# uController.net
KiCad netlist of a schematic drawn in Altium Designer
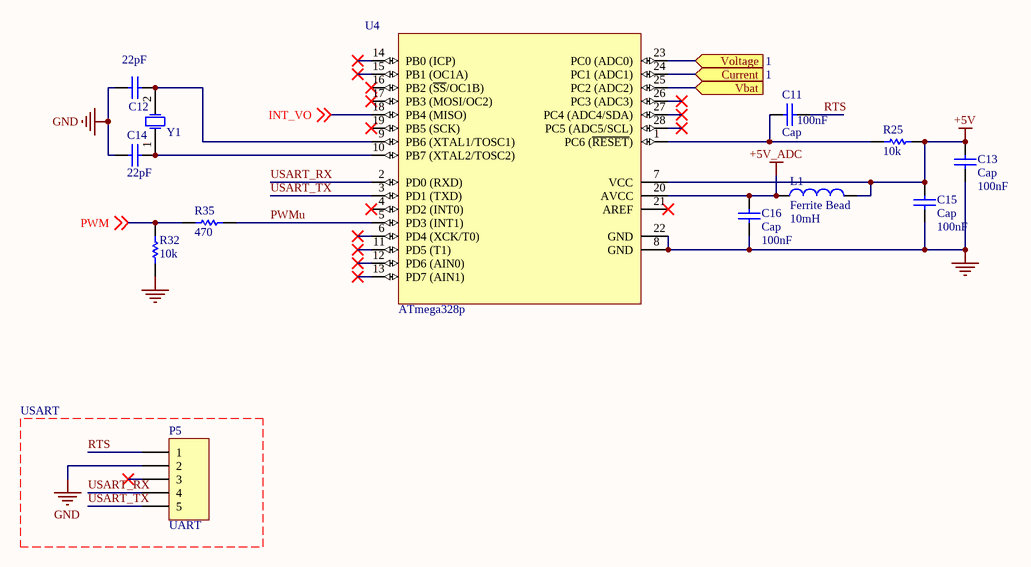
[diagram p0: uController.SchDoc]

(export (version "E")
  (design (tool "Eeschema 10.0.6"))
  (components
    (comp (ref "C11")
      (value "Cap")
      (footprint "6-0805_M")
      (description "Capacitor")
      (fields (field (name "ALTIUM_VALUE") "100nF") (field (name "PUBLISHER") "Altium Limited"))
      (libsource (lib "Miscellaneous Devices") (part "Cap"))
    )
    (comp (ref "C12")
      (value "22pF")
      (footprint "C0805")
      (description "Capacitor (Semiconductor SIM Model)")
      (fields (field (name "PUBLISHER") "Altium Limited"))
      (libsource (lib "Miscellaneous Devices") (part "Cap Semi"))
    )
    (comp (ref "C13")
      (value "Cap")
      (footprint "PCB1_corrosao:C1210_M")
      (description "Capacitor")
      (fields (field (name "ALTIUM_VALUE") "100nF") (field (name "PUBLISHER") "Altium Limited"))
      (libsource (lib "Miscellaneous Devices") (part "Cap"))
    )
    (comp (ref "C14")
      (value "22pF")
      (footprint "C0805")
      (description "Capacitor (Semiconductor SIM Model)")
      (fields (field (name "PUBLISHER") "Altium Limited"))
      (libsource (lib "Miscellaneous Devices") (part "Cap Semi"))
    )
    (comp (ref "C15")
      (value "Cap")
      (footprint "6-0805_M")
      (description "Capacitor")
      (fields (field (name "ALTIUM_VALUE") "100nF") (field (name "PUBLISHER") "Altium Limited"))
      (libsource (lib "Miscellaneous Devices") (part "Cap"))
    )
    (comp (ref "C16")
      (value "Cap")
      (footprint "6-0805_M")
      (description "Capacitor")
      (fields (field (name "ALTIUM_VALUE") "100nF") (field (name "PUBLISHER") "Altium Limited"))
      (libsource (lib "Miscellaneous Devices") (part "Cap"))
    )
    (comp (ref "L1")
      (value "Ferrite Bead")
      (footprint "6-0805_M")
      (description "Inductor")
      (fields (field (name "ALTIUM_VALUE") "10mH") (field (name "PUBLISHER") "Altium Limited"))
      (libsource (lib "Miscellaneous Devices") (part "Inductor"))
    )
    (comp (ref "P5")
      (value "UART")
      (footprint "HDR1X5")
      (description "Header, 5-Pin")
      (fields (field (name "PUBLISHER") "Altium Limited"))
      (libsource (lib "Miscellaneous Connectors") (part "Header 5"))
    )
    (comp (ref "R25")
      (value "10k")
      (footprint "6-0805_M")
      (description "Resistor")
      (fields (field (name "Comment") "Res1") (field (name "PUBLISHER") "Altium Limited"))
      (libsource (lib "Miscellaneous Devices") (part "Res1"))
    )
    (comp (ref "R32")
      (value "10k")
      (footprint "6-0805_M")
      (description "Resistor")
      (fields (field (name "Comment") "Res1") (field (name "PUBLISHER") "Altium Limited"))
      (libsource (lib "Miscellaneous Devices") (part "Res1"))
    )
    (comp (ref "R35")
      (value "470")
      (footprint "6-0805_M")
      (description "Resistor")
      (fields (field (name "PUBLISHER") "Altium Limited"))
      (libsource (lib "ControladorCarga") (part "Res1"))
    )
    (comp (ref "U4")
      (value "ATmega328p")
      (footprint "28P3")
      (description "8-Bit AVR Microcontroller with 8K Bytes of In-System Programmable Flash Memory")
      (fields (field (name "PUBLISHER") "Altium Limited"))
      (libsource (lib "Atmel Microcontroller 8-Bit AVR") (part "ATmega8-16PI"))
    )
    (comp (ref "Y1")
      (value "~")
      (footprint "PCB1_corrosao:HC-49U")
      (description "Crystal Oscillator")
      (libsource (lib "Schematic") (part "Crystal"))
    )
  )
  (nets
    (net (code "1") (name "+5V") (class "Default")
      (node (ref "C13") (pin "1") (pinfunction "1_1") (pintype "passive"))
      (node (ref "C15") (pin "1") (pinfunction "1_1") (pintype "passive"))
      (node (ref "L1") (pin "2") (pinfunction "2_2") (pintype "passive"))
      (node (ref "R25") (pin "2") (pinfunction "2_2") (pintype "passive"))
      (node (ref "U4") (pin "7") (pinfunction "VCC_7") (pintype "power_in"))
    )
    (net (code "2") (name "+5V_ADC") (class "Default")
      (node (ref "C16") (pin "1") (pinfunction "1_1") (pintype "passive"))
      (node (ref "L1") (pin "1") (pinfunction "1_1") (pintype "passive"))
      (node (ref "U4") (pin "20") (pinfunction "AVCC_20") (pintype "power_in"))
    )
    (net (code "3") (name "/Current") (class "Default")
      (node (ref "U4") (pin "24") (pinfunction "PC1_(ADC1)_24") (pintype "bidirectional"))
    )
    (net (code "4") (name "/PWMu") (class "Default")
      (node (ref "R35") (pin "2") (pinfunction "2_2") (pintype "passive"))
      (node (ref "U4") (pin "5") (pinfunction "PD3_(INT1)_5") (pintype "bidirectional"))
    )
    (net (code "5") (name "/RTS") (class "Default")
      (node (ref "C11") (pin "2") (pinfunction "2_2") (pintype "passive"))
      (node (ref "P5") (pin "1") (pinfunction "1_1") (pintype "passive"))
    )
    (net (code "6") (name "/USART_RX") (class "Default")
      (node (ref "P5") (pin "4") (pinfunction "4_4") (pintype "passive"))
      (node (ref "U4") (pin "2") (pinfunction "PD0_(RXD)_2") (pintype "bidirectional"))
    )
    (net (code "7") (name "/USART_TX") (class "Default")
      (node (ref "P5") (pin "5") (pinfunction "5_5") (pintype "passive"))
      (node (ref "U4") (pin "3") (pinfunction "PD1_(TXD)_3") (pintype "bidirectional"))
    )
    (net (code "8") (name "/Vbat") (class "Default")
      (node (ref "U4") (pin "25") (pinfunction "PC2_(ADC2)_25") (pintype "bidirectional"))
    )
    (net (code "9") (name "/Voltage") (class "Default")
      (node (ref "U4") (pin "23") (pinfunction "PC0_(ADC0)_23") (pintype "bidirectional"))
    )
    (net (code "10") (name "GND") (class "Default")
      (node (ref "C12") (pin "1") (pinfunction "1_1") (pintype "passive"))
      (node (ref "C13") (pin "2") (pinfunction "2_2") (pintype "passive"))
      (node (ref "C14") (pin "1") (pinfunction "1_1") (pintype "passive"))
      (node (ref "C15") (pin "2") (pinfunction "2_2") (pintype "passive"))
      (node (ref "C16") (pin "2") (pinfunction "2_2") (pintype "passive"))
      (node (ref "P5") (pin "2") (pinfunction "2_2") (pintype "passive"))
      (node (ref "R32") (pin "1") (pinfunction "1_1") (pintype "passive"))
      (node (ref "U4") (pin "22") (pinfunction "GND_22") (pintype "power_in"))
      (node (ref "U4") (pin "8") (pinfunction "GND_8") (pintype "power_in"))
    )
    (net (code "11") (name "INT_VO") (class "Default")
      (node (ref "U4") (pin "18") (pinfunction "PB4_(MISO)_18") (pintype "bidirectional"))
    )
    (net (code "12") (name "Net-(U4-PB6_(XTAL1{slash}TOSC1))") (class "Default")
      (node (ref "C12") (pin "2") (pinfunction "2_2") (pintype "passive"))
      (node (ref "U4") (pin "9") (pinfunction "PB6_(XTAL1/TOSC1)_9") (pintype "bidirectional"))
      (node (ref "Y1") (pin "2") (pinfunction "OSC2_2") (pintype "passive"))
    )
    (net (code "13") (name "Net-(U4-PB7_(XTAL2{slash}TOSC2))") (class "Default")
      (node (ref "C14") (pin "2") (pinfunction "2_2") (pintype "passive"))
      (node (ref "U4") (pin "10") (pinfunction "PB7_(XTAL2/TOSC2)_10") (pintype "bidirectional"))
      (node (ref "Y1") (pin "1") (pinfunction "OSC1_1") (pintype "passive"))
    )
    (net (code "14") (name "Net-(U4-PC6_(~{RESET}))") (class "Default")
      (node (ref "C11") (pin "1") (pinfunction "1_1") (pintype "passive"))
      (node (ref "R25") (pin "1") (pinfunction "1_1") (pintype "passive"))
      (node (ref "U4") (pin "1") (pinfunction "PC6_(~{RESET})_1") (pintype "bidirectional"))
    )
    (net (code "15") (name "PWM") (class "Default")
      (node (ref "R32") (pin "2") (pinfunction "2_2") (pintype "passive"))
      (node (ref "R35") (pin "1") (pinfunction "1_1") (pintype "passive"))
    )
    (net (code "16") (name "unconnected-(P5-Pad3)") (class "Default")
      (node (ref "P5") (pin "3") (pinfunction "3_3") (pintype "passive+no_connect"))
    )
    (net (code "17") (name "unconnected-(U4-AREF-Pad21)") (class "Default")
      (node (ref "U4") (pin "21") (pinfunction "AREF_21") (pintype "passive+no_connect"))
    )
    (net (code "18") (name "unconnected-(U4-PB0_(ICP)-Pad14)") (class "Default")
      (node (ref "U4") (pin "14") (pinfunction "PB0_(ICP)_14") (pintype "bidirectional+no_connect"))
    )
    (net (code "19") (name "unconnected-(U4-PB1_(OC1A)-Pad15)") (class "Default")
      (node (ref "U4") (pin "15") (pinfunction "PB1_(OC1A)_15") (pintype "bidirectional+no_connect"))
    )
    (net (code "20") (name "unconnected-(U4-PB2_(~{SS}{slash}OC1B)-Pad16)") (class "Default")
      (node (ref "U4") (pin "16") (pinfunction "PB2_(~{SS}/OC1B)_16") (pintype "bidirectional+no_connect"))
    )
    (net (code "21") (name "unconnected-(U4-PB3_(MOSI{slash}OC2)-Pad17)") (class "Default")
      (node (ref "U4") (pin "17") (pinfunction "PB3_(MOSI/OC2)_17") (pintype "bidirectional+no_connect"))
    )
    (net (code "22") (name "unconnected-(U4-PB5_(SCK)-Pad19)") (class "Default")
      (node (ref "U4") (pin "19") (pinfunction "PB5_(SCK)_19") (pintype "bidirectional+no_connect"))
    )
    (net (code "23") (name "unconnected-(U4-PC3_(ADC3)-Pad26)") (class "Default")
      (node (ref "U4") (pin "26") (pinfunction "PC3_(ADC3)_26") (pintype "bidirectional+no_connect"))
    )
    (net (code "24") (name "unconnected-(U4-PC4_(ADC4{slash}SDA)-Pad27)") (class "Default")
      (node (ref "U4") (pin "27") (pinfunction "PC4_(ADC4/SDA)_27") (pintype "bidirectional+no_connect"))
    )
    (net (code "25") (name "unconnected-(U4-PC5_(ADC5{slash}SCL)-Pad28)") (class "Default")
      (node (ref "U4") (pin "28") (pinfunction "PC5_(ADC5/SCL)_28") (pintype "bidirectional+no_connect"))
    )
    (net (code "26") (name "unconnected-(U4-PD2_(INT0)-Pad4)") (class "Default")
      (node (ref "U4") (pin "4") (pinfunction "PD2_(INT0)_4") (pintype "bidirectional+no_connect"))
    )
    (net (code "27") (name "unconnected-(U4-PD4_(XCK{slash}T0)-Pad6)") (class "Default")
      (node (ref "U4") (pin "6") (pinfunction "PD4_(XCK/T0)_6") (pintype "bidirectional+no_connect"))
    )
    (net (code "28") (name "unconnected-(U4-PD5_(T1)-Pad11)") (class "Default")
      (node (ref "U4") (pin "11") (pinfunction "PD5_(T1)_11") (pintype "bidirectional+no_connect"))
    )
    (net (code "29") (name "unconnected-(U4-PD6_(AIN0)-Pad12)") (class "Default")
      (node (ref "U4") (pin "12") (pinfunction "PD6_(AIN0)_12") (pintype "bidirectional+no_connect"))
    )
    (net (code "30") (name "unconnected-(U4-PD7_(AIN1)-Pad13)") (class "Default")
      (node (ref "U4") (pin "13") (pinfunction "PD7_(AIN1)_13") (pintype "bidirectional+no_connect"))
    )
  )
)
